# ArduinoProMiniESP2866Adapter.net
KiCad netlist of a schematic drawn in EAGLE
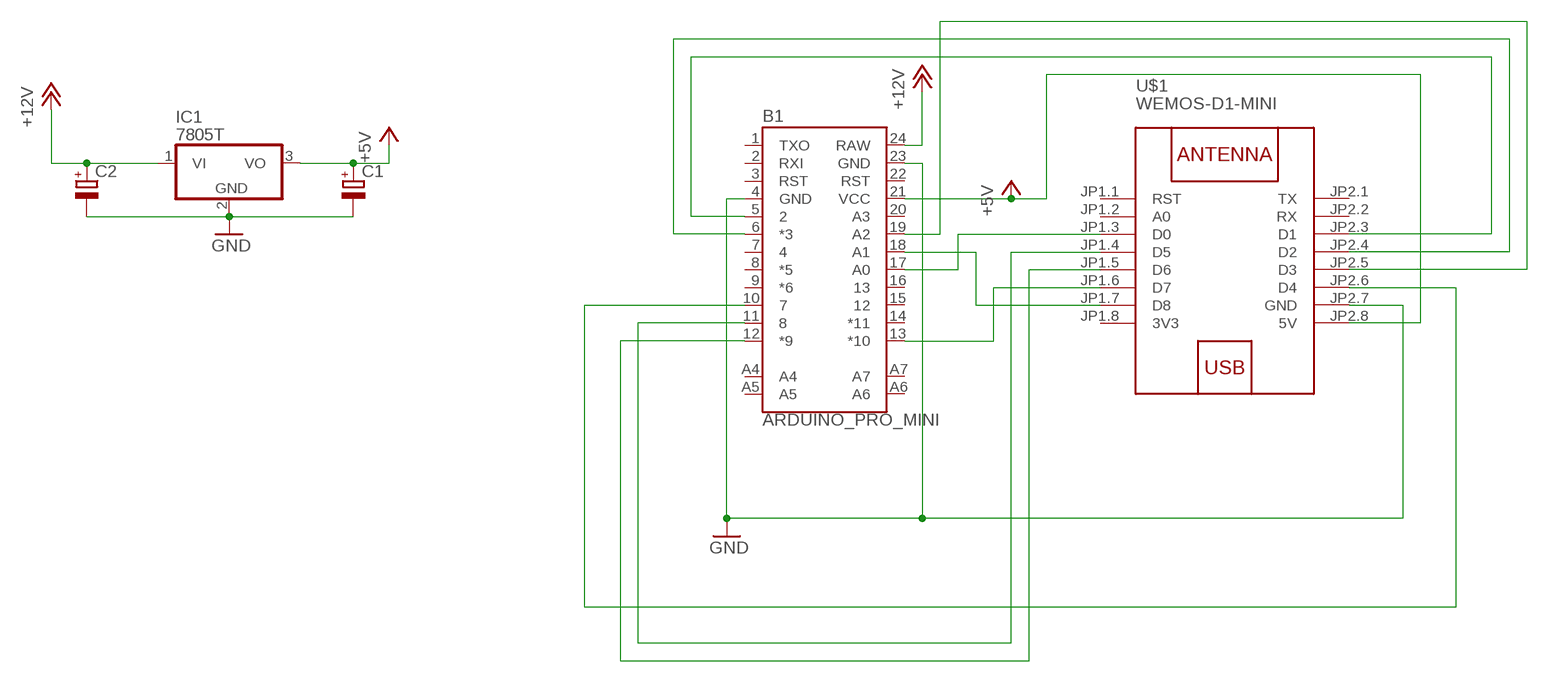
[diagram p0: schematic, sheet 1]

(export (version "E")
  (design (tool "Eeschema 10.0.6"))
  (components
    (comp (ref "B1")
      (value "ARDUINO_PRO_MINI")
      (footprint "eagle-import:ARDUINO_PRO_MINI")
      (libsource (lib "eagle-import") (part "ARDUINO_PRO_MINI"))
    )
    (comp (ref "C1")
      (value "CPOL-EUE2-4")
      (footprint "eagle-import:E2-4")
      (libsource (lib "eagle-import") (part "CPOL-EUE2-4"))
    )
    (comp (ref "C2")
      (value "CPOL-EUE2-4")
      (footprint "eagle-import:E2-4")
      (libsource (lib "eagle-import") (part "CPOL-EUE2-4"))
    )
    (comp (ref "IC1")
      (value "7805T")
      (footprint "eagle-import:TO220H")
      (libsource (lib "eagle-import") (part "78T05"))
    )
    (comp (ref "U$1")
      (value "WEMOS-D1-MINI")
      (footprint "eagle-import:WEMOS-D1-MINI")
      (libsource (lib "eagle-import") (part "WEMOS-D1-MINI"))
    )
  )
  (nets
    (net (code "1") (name "+5V") (class "Default")
      (node (ref "B1") (pin "21") (pinfunction "VCC_21") (pintype "power_in"))
      (node (ref "C1") (pin "+") (pinfunction "+_+") (pintype "passive"))
      (node (ref "IC1") (pin "3") (pinfunction "VO_3") (pintype "passive"))
      (node (ref "U$1") (pin "JP2.8") (pinfunction "5V_JP2.8") (pintype "power_in"))
    )
    (net (code "2") (name "+12V") (class "Default")
      (node (ref "B1") (pin "24") (pinfunction "RAW_24") (pintype "power_in"))
      (node (ref "C2") (pin "+") (pinfunction "+_+") (pintype "passive"))
      (node (ref "IC1") (pin "1") (pinfunction "VI_1") (pintype "input"))
    )
    (net (code "3") (name "/3V3") (class "Default")
      (node (ref "U$1") (pin "JP1.8") (pinfunction "3V3_JP1.8") (pintype "power_in"))
    )
    (net (code "4") (name "GND") (class "Default")
      (node (ref "B1") (pin "23") (pinfunction "GND_23") (pintype "power_in"))
      (node (ref "B1") (pin "4") (pinfunction "GND_4") (pintype "power_in"))
      (node (ref "C1") (pin "-") (pinfunction "-_-") (pintype "passive"))
      (node (ref "C2") (pin "-") (pinfunction "-_-") (pintype "passive"))
      (node (ref "IC1") (pin "2") (pinfunction "GND_2") (pintype "passive"))
      (node (ref "U$1") (pin "JP2.7") (pinfunction "GND_JP2.7") (pintype "power_in"))
    )
    (net (code "5") (name "Net-(B1-*3)") (class "Default")
      (node (ref "B1") (pin "6") (pinfunction "*3_6") (pintype "bidirectional"))
      (node (ref "U$1") (pin "JP2.4") (pinfunction "D2_JP2.4") (pintype "bidirectional"))
    )
    (net (code "6") (name "Net-(B1-*9)") (class "Default")
      (node (ref "B1") (pin "12") (pinfunction "*9_12") (pintype "bidirectional"))
      (node (ref "U$1") (pin "JP1.5") (pinfunction "D6_JP1.5") (pintype "bidirectional"))
    )
    (net (code "7") (name "Net-(B1-*10)") (class "Default")
      (node (ref "B1") (pin "13") (pinfunction "*10_13") (pintype "bidirectional"))
      (node (ref "U$1") (pin "JP1.6") (pinfunction "D7_JP1.6") (pintype "bidirectional"))
    )
    (net (code "8") (name "Net-(B1-2)") (class "Default")
      (node (ref "B1") (pin "5") (pinfunction "2_5") (pintype "bidirectional"))
      (node (ref "U$1") (pin "JP2.3") (pinfunction "D1_JP2.3") (pintype "bidirectional"))
    )
    (net (code "9") (name "Net-(B1-7)") (class "Default")
      (node (ref "B1") (pin "10") (pinfunction "7_10") (pintype "bidirectional"))
      (node (ref "U$1") (pin "JP2.6") (pinfunction "D4_JP2.6") (pintype "bidirectional"))
    )
    (net (code "10") (name "Net-(B1-8)") (class "Default")
      (node (ref "B1") (pin "11") (pinfunction "8_11") (pintype "bidirectional"))
      (node (ref "U$1") (pin "JP1.4") (pinfunction "D5_JP1.4") (pintype "bidirectional"))
    )
    (net (code "11") (name "Net-(B1-A0)") (class "Default")
      (node (ref "B1") (pin "17") (pinfunction "A0_17") (pintype "bidirectional"))
      (node (ref "U$1") (pin "JP1.3") (pinfunction "D0_JP1.3") (pintype "bidirectional"))
    )
    (net (code "12") (name "Net-(B1-A1)") (class "Default")
      (node (ref "B1") (pin "18") (pinfunction "A1_18") (pintype "bidirectional"))
      (node (ref "U$1") (pin "JP1.7") (pinfunction "D8_JP1.7") (pintype "bidirectional"))
    )
    (net (code "13") (name "Net-(B1-A2)") (class "Default")
      (node (ref "B1") (pin "19") (pinfunction "A2_19") (pintype "bidirectional"))
      (node (ref "U$1") (pin "JP2.5") (pinfunction "D3_JP2.5") (pintype "bidirectional"))
    )
    (net (code "14") (name "unconnected-(B1-*5-Pad8)") (class "Default")
      (node (ref "B1") (pin "8") (pinfunction "*5_8") (pintype "bidirectional"))
    )
    (net (code "15") (name "unconnected-(B1-*6-Pad9)") (class "Default")
      (node (ref "B1") (pin "9") (pinfunction "*6_9") (pintype "bidirectional"))
    )
    (net (code "16") (name "unconnected-(B1-*11-Pad14)") (class "Default")
      (node (ref "B1") (pin "14") (pinfunction "*11_14") (pintype "bidirectional"))
    )
    (net (code "17") (name "unconnected-(B1-4-Pad7)") (class "Default")
      (node (ref "B1") (pin "7") (pinfunction "4_7") (pintype "bidirectional"))
    )
    (net (code "18") (name "unconnected-(B1-12-Pad15)") (class "Default")
      (node (ref "B1") (pin "15") (pinfunction "12_15") (pintype "bidirectional"))
    )
    (net (code "19") (name "unconnected-(B1-13-Pad16)") (class "Default")
      (node (ref "B1") (pin "16") (pinfunction "13_16") (pintype "bidirectional"))
    )
    (net (code "20") (name "unconnected-(B1-A3-Pad20)") (class "Default")
      (node (ref "B1") (pin "20") (pinfunction "A3_20") (pintype "bidirectional"))
    )
    (net (code "21") (name "unconnected-(B1-PadA4)") (class "Default")
      (node (ref "B1") (pin "A4") (pinfunction "A4_A4") (pintype "bidirectional"))
    )
    (net (code "22") (name "unconnected-(B1-PadA5)") (class "Default")
      (node (ref "B1") (pin "A5") (pinfunction "A5_A5") (pintype "bidirectional"))
    )
    (net (code "23") (name "unconnected-(B1-PadA6)") (class "Default")
      (node (ref "B1") (pin "A6") (pinfunction "A6_A6") (pintype "bidirectional"))
    )
    (net (code "24") (name "unconnected-(B1-PadA7)") (class "Default")
      (node (ref "B1") (pin "A7") (pinfunction "A7_A7") (pintype "bidirectional"))
    )
    (net (code "25") (name "unconnected-(B1-RST-Pad3)") (class "Default")
      (node (ref "B1") (pin "3") (pinfunction "RST_3") (pintype "bidirectional"))
    )
    (net (code "26") (name "unconnected-(B1-RST-Pad22)") (class "Default")
      (node (ref "B1") (pin "22") (pinfunction "RST_22") (pintype "bidirectional"))
    )
    (net (code "27") (name "unconnected-(B1-RXI-Pad2)") (class "Default")
      (node (ref "B1") (pin "2") (pinfunction "RXI_2") (pintype "bidirectional"))
    )
    (net (code "28") (name "unconnected-(B1-TXO-Pad1)") (class "Default")
      (node (ref "B1") (pin "1") (pinfunction "TXO_1") (pintype "bidirectional"))
    )
    (net (code "29") (name "unconnected-(U$1-A0-PadJP1.2)") (class "Default")
      (node (ref "U$1") (pin "JP1.2") (pinfunction "A0_JP1.2") (pintype "bidirectional"))
    )
    (net (code "30") (name "unconnected-(U$1-RST-PadJP1.1)") (class "Default")
      (node (ref "U$1") (pin "JP1.1") (pinfunction "RST_JP1.1") (pintype "bidirectional"))
    )
    (net (code "31") (name "unconnected-(U$1-RX-PadJP2.2)") (class "Default")
      (node (ref "U$1") (pin "JP2.2") (pinfunction "RX_JP2.2") (pintype "bidirectional"))
    )
    (net (code "32") (name "unconnected-(U$1-TX-PadJP2.1)") (class "Default")
      (node (ref "U$1") (pin "JP2.1") (pinfunction "TX_JP2.1") (pintype "bidirectional"))
    )
  )
)
